# 2_AASTM32-MCU.net
KiCad netlist of a schematic drawn in Altium Designer
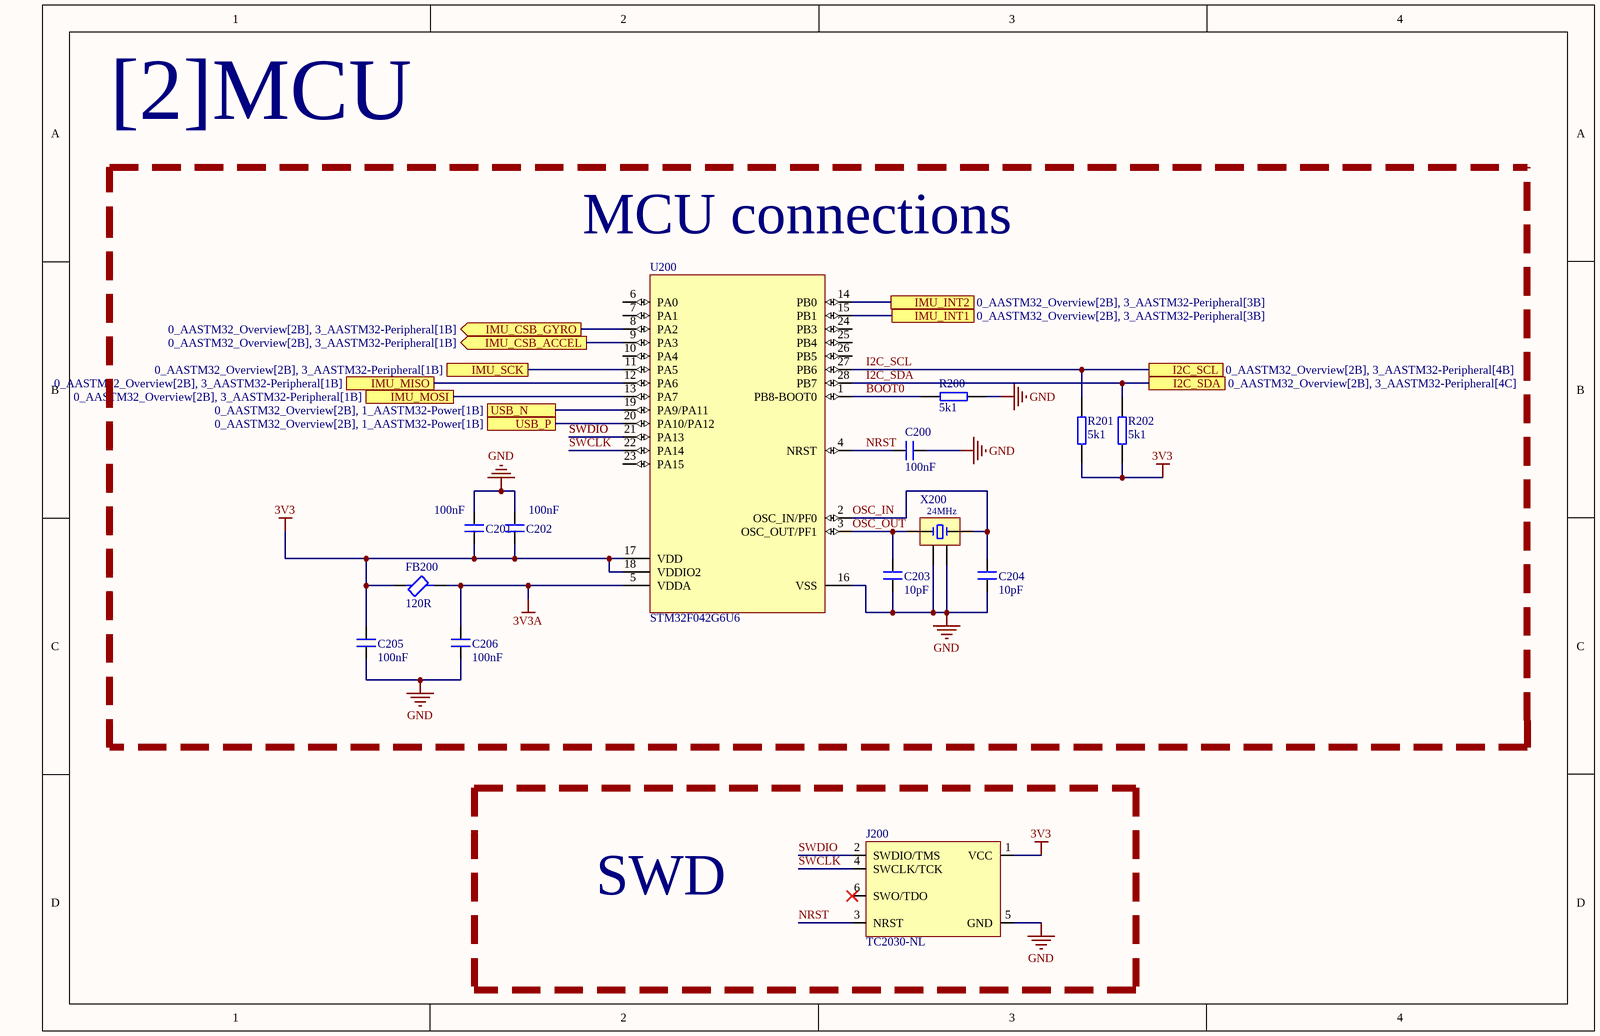
[diagram p0: 2_AASTM32-MCU.SchDoc]

(export (version "E")
  (design (tool "Eeschema 10.0.6"))
  (components
    (comp (ref "C200")
      (value "100nF")
      (footprint "0603 CAP")
      (fields
        (field (name "MANUFACTURER") "Samsung")
        (field (name "MANUFACTURER PART NUMBER") "CL10A475KA8NQNC")
      )
      (libsource (lib "GenerALI") (part "0603 4u7 CAP"))
    )
    (comp (ref "C201")
      (value "100nF")
      (footprint "0603 CAP")
      (fields
        (field (name "MANUFACTURER") "Samsung")
        (field (name "MANUFACTURER PART NUMBER") "CL10A475KA8NQNC")
      )
      (libsource (lib "GenerALI") (part "0603 4u7 CAP"))
    )
    (comp (ref "C202")
      (value "100nF")
      (footprint "0603 CAP")
      (fields
        (field (name "MANUFACTURER") "Samsung")
        (field (name "MANUFACTURER PART NUMBER") "CL10A475KA8NQNC")
      )
      (libsource (lib "GenerALI") (part "0603 4u7 CAP"))
    )
    (comp (ref "C203")
      (value "10pF")
      (footprint "0603 CAP")
      (fields
        (field (name "MANUFACTURER") "Samsung")
        (field (name "MANUFACTURER PART NUMBER") "CL10A475KA8NQNC")
      )
      (libsource (lib "GenerALI") (part "0603 4u7 CAP"))
    )
    (comp (ref "C204")
      (value "10pF")
      (footprint "0603 CAP")
      (fields
        (field (name "MANUFACTURER") "Samsung")
        (field (name "MANUFACTURER PART NUMBER") "CL10A475KA8NQNC")
      )
      (libsource (lib "GenerALI") (part "0603 4u7 CAP"))
    )
    (comp (ref "C205")
      (value "100nF")
      (footprint "0603 CAP")
      (fields
        (field (name "MANUFACTURER") "Samsung")
        (field (name "MANUFACTURER PART NUMBER") "CL10A475KA8NQNC")
      )
      (libsource (lib "GenerALI") (part "0603 4u7 CAP"))
    )
    (comp (ref "C206")
      (value "100nF")
      (footprint "0603 CAP")
      (fields
        (field (name "MANUFACTURER") "Samsung")
        (field (name "MANUFACTURER PART NUMBER") "CL10A475KA8NQNC")
      )
      (libsource (lib "GenerALI") (part "0603 4u7 CAP"))
    )
    (comp (ref "FB200")
      (value "120R")
      (footprint "0402 RES")
      (description "Ferrite Chip, 1 Function(s), 0.9A, 2 Pin(s)\r\nBLM15PD121SN1D")
      (fields
        (field (name "MANUFACTURER") "Murata")
        (field (name "MANUFACTURER PART NUMBER") "BLM15PD121SN1D")
      )
      (libsource (lib "GenerALI") (part "Ferritte Bead 120R 0402"))
    )
    (comp (ref "J200")
      (value "TC2030-NL")
      (footprint "TC2030-NL-FP")
      (description "Tag-Connect No-Solder SWD Debug Connector (No Legs) DO NOT PLACE")
      (fields
        (field (name "MANUFACTURER") "Tag-Connect")
        (field (name "MANUFACTURER PART NUMBER") "TC2030-NL-FP")
      )
      (libsource (lib "Schematic-Lib-PhilsLab") (part "TC2030-NL"))
    )
    (comp (ref "R200")
      (value "5k1")
      (footprint "0603 RES")
      (libsource (lib "GenerALI") (part "0603 10k RES"))
    )
    (comp (ref "R201")
      (value "5k1")
      (footprint "0603 RES")
      (libsource (lib "GenerALI") (part "0603 10k RES"))
    )
    (comp (ref "R202")
      (value "5k1")
      (footprint "0603 RES")
      (libsource (lib "GenerALI") (part "0603 10k RES"))
    )
    (comp (ref "U200")
      (value "STM32F042G6U6")
      (footprint "UFQFPN28")
      (fields (field (name "MANUFACTURER") "STMicroelectronics"))
      (libsource (lib "GenerALI") (part "STM32F042G6U6"))
    )
    (comp (ref "X200")
      (value "TSX-3225 24.0000MF15X")
      (footprint "3225")
      (description "Crystals 24MHz 10ppm 9pF-40C +85C")
      (libsource (lib "GenerALI") (part "TSX-3225 24.0000MF15X-AC3"))
    )
  )
  (nets
    (net (code "1") (name "/BOOT0") (class "Default")
      (node (ref "R200") (pin "2") (pinfunction "2_2") (pintype "passive"))
      (node (ref "U200") (pin "1") (pinfunction "PB8-BOOT0_1") (pintype "bidirectional"))
    )
    (net (code "2") (name "/I2C_SCL") (class "Default")
      (node (ref "R201") (pin "1") (pinfunction "1_1") (pintype "passive"))
      (node (ref "U200") (pin "27") (pinfunction "PB6_27") (pintype "bidirectional"))
    )
    (net (code "3") (name "/I2C_SDA") (class "Default")
      (node (ref "R202") (pin "1") (pinfunction "1_1") (pintype "passive"))
      (node (ref "U200") (pin "28") (pinfunction "PB7_28") (pintype "bidirectional"))
    )
    (net (code "4") (name "/IMU_CSB_ACCEL") (class "Default")
      (node (ref "U200") (pin "9") (pinfunction "PA3_9") (pintype "bidirectional"))
    )
    (net (code "5") (name "/IMU_CSB_GYRO") (class "Default")
      (node (ref "U200") (pin "8") (pinfunction "PA2_8") (pintype "bidirectional"))
    )
    (net (code "6") (name "/IMU_INT1") (class "Default")
      (node (ref "U200") (pin "15") (pinfunction "PB1_15") (pintype "bidirectional"))
    )
    (net (code "7") (name "/IMU_INT2") (class "Default")
      (node (ref "U200") (pin "14") (pinfunction "PB0_14") (pintype "bidirectional"))
    )
    (net (code "8") (name "/IMU_MISO") (class "Default")
      (node (ref "U200") (pin "12") (pinfunction "PA6_12") (pintype "bidirectional"))
    )
    (net (code "9") (name "/IMU_MOSI") (class "Default")
      (node (ref "U200") (pin "13") (pinfunction "PA7_13") (pintype "bidirectional"))
    )
    (net (code "10") (name "/IMU_SCK") (class "Default")
      (node (ref "U200") (pin "11") (pinfunction "PA5_11") (pintype "bidirectional"))
    )
    (net (code "11") (name "/NRST") (class "Default")
      (node (ref "C200") (pin "2") (pinfunction "2_2") (pintype "passive"))
      (node (ref "J200") (pin "3") (pinfunction "NRST_3") (pintype "passive"))
      (node (ref "U200") (pin "4") (pinfunction "NRST_4") (pintype "bidirectional"))
    )
    (net (code "12") (name "/OSC_IN") (class "Default")
      (node (ref "C204") (pin "2") (pinfunction "2_2") (pintype "passive"))
      (node (ref "U200") (pin "2") (pinfunction "OSC_IN/PF0_2") (pintype "bidirectional"))
      (node (ref "X200") (pin "3") (pinfunction "3_3") (pintype "passive"))
    )
    (net (code "13") (name "/OSC_OUT") (class "Default")
      (node (ref "C203") (pin "2") (pinfunction "2_2") (pintype "passive"))
      (node (ref "U200") (pin "3") (pinfunction "OSC_OUT/PF1_3") (pintype "bidirectional"))
      (node (ref "X200") (pin "1") (pinfunction "1_1") (pintype "passive"))
    )
    (net (code "14") (name "/SWCLK") (class "Default")
      (node (ref "J200") (pin "4") (pinfunction "SWCLK/TCK_4") (pintype "passive"))
      (node (ref "U200") (pin "22") (pinfunction "PA14_22") (pintype "bidirectional"))
    )
    (net (code "15") (name "/SWDIO") (class "Default")
      (node (ref "J200") (pin "2") (pinfunction "SWDIO/TMS_2") (pintype "passive"))
      (node (ref "U200") (pin "21") (pinfunction "PA13_21") (pintype "bidirectional"))
    )
    (net (code "16") (name "/USB_N") (class "Default")
      (node (ref "U200") (pin "19") (pinfunction "PA9/PA11_19") (pintype "bidirectional"))
    )
    (net (code "17") (name "/USB_P") (class "Default")
      (node (ref "U200") (pin "20") (pinfunction "PA10/PA12_20") (pintype "bidirectional"))
    )
    (net (code "18") (name "3V3") (class "Default")
      (node (ref "C201") (pin "2") (pinfunction "2_2") (pintype "passive"))
      (node (ref "C202") (pin "2") (pinfunction "2_2") (pintype "passive"))
      (node (ref "C205") (pin "2") (pinfunction "2_2") (pintype "passive"))
      (node (ref "FB200") (pin "1") (pinfunction "1_1") (pintype "passive"))
      (node (ref "J200") (pin "1") (pinfunction "VCC_1") (pintype "passive"))
      (node (ref "R201") (pin "2") (pinfunction "2_2") (pintype "passive"))
      (node (ref "R202") (pin "2") (pinfunction "2_2") (pintype "passive"))
      (node (ref "U200") (pin "17") (pinfunction "VDD_17") (pintype "power_in"))
      (node (ref "U200") (pin "18") (pinfunction "VDDIO2_18") (pintype "power_in"))
    )
    (net (code "19") (name "3V3A") (class "Default")
      (node (ref "C206") (pin "2") (pinfunction "2_2") (pintype "passive"))
      (node (ref "FB200") (pin "2") (pinfunction "2_2") (pintype "passive"))
      (node (ref "U200") (pin "5") (pinfunction "VDDA_5") (pintype "power_in"))
    )
    (net (code "20") (name "GND") (class "Default")
      (node (ref "C200") (pin "1") (pinfunction "1_1") (pintype "passive"))
      (node (ref "C201") (pin "1") (pinfunction "1_1") (pintype "passive"))
      (node (ref "C202") (pin "1") (pinfunction "1_1") (pintype "passive"))
      (node (ref "C203") (pin "1") (pinfunction "1_1") (pintype "passive"))
      (node (ref "C204") (pin "1") (pinfunction "1_1") (pintype "passive"))
      (node (ref "C205") (pin "1") (pinfunction "1_1") (pintype "passive"))
      (node (ref "C206") (pin "1") (pinfunction "1_1") (pintype "passive"))
      (node (ref "J200") (pin "5") (pinfunction "GND_5") (pintype "passive"))
      (node (ref "R200") (pin "1") (pinfunction "1_1") (pintype "passive"))
      (node (ref "U200") (pin "16") (pinfunction "VSS_16") (pintype "power_in"))
      (node (ref "X200") (pin "2") (pinfunction "2_2") (pintype "passive"))
      (node (ref "X200") (pin "4") (pinfunction "4_4") (pintype "passive"))
    )
    (net (code "21") (name "unconnected-(J200-SWO{slash}TDO-Pad6)") (class "Default")
      (node (ref "J200") (pin "6") (pinfunction "SWO/TDO_6") (pintype "passive+no_connect"))
    )
    (net (code "22") (name "unconnected-(U200-PA0-Pad6)") (class "Default")
      (node (ref "U200") (pin "6") (pinfunction "PA0_6") (pintype "bidirectional"))
    )
    (net (code "23") (name "unconnected-(U200-PA1-Pad7)") (class "Default")
      (node (ref "U200") (pin "7") (pinfunction "PA1_7") (pintype "bidirectional"))
    )
    (net (code "24") (name "unconnected-(U200-PA4-Pad10)") (class "Default")
      (node (ref "U200") (pin "10") (pinfunction "PA4_10") (pintype "bidirectional"))
    )
    (net (code "25") (name "unconnected-(U200-PA15-Pad23)") (class "Default")
      (node (ref "U200") (pin "23") (pinfunction "PA15_23") (pintype "bidirectional"))
    )
    (net (code "26") (name "unconnected-(U200-PB3-Pad24)") (class "Default")
      (node (ref "U200") (pin "24") (pinfunction "PB3_24") (pintype "bidirectional"))
    )
    (net (code "27") (name "unconnected-(U200-PB4-Pad25)") (class "Default")
      (node (ref "U200") (pin "25") (pinfunction "PB4_25") (pintype "bidirectional"))
    )
    (net (code "28") (name "unconnected-(U200-PB5-Pad26)") (class "Default")
      (node (ref "U200") (pin "26") (pinfunction "PB5_26") (pintype "bidirectional"))
    )
  )
)
